# S3220A5.net
KiCad netlist of a schematic drawn in Altium Designer
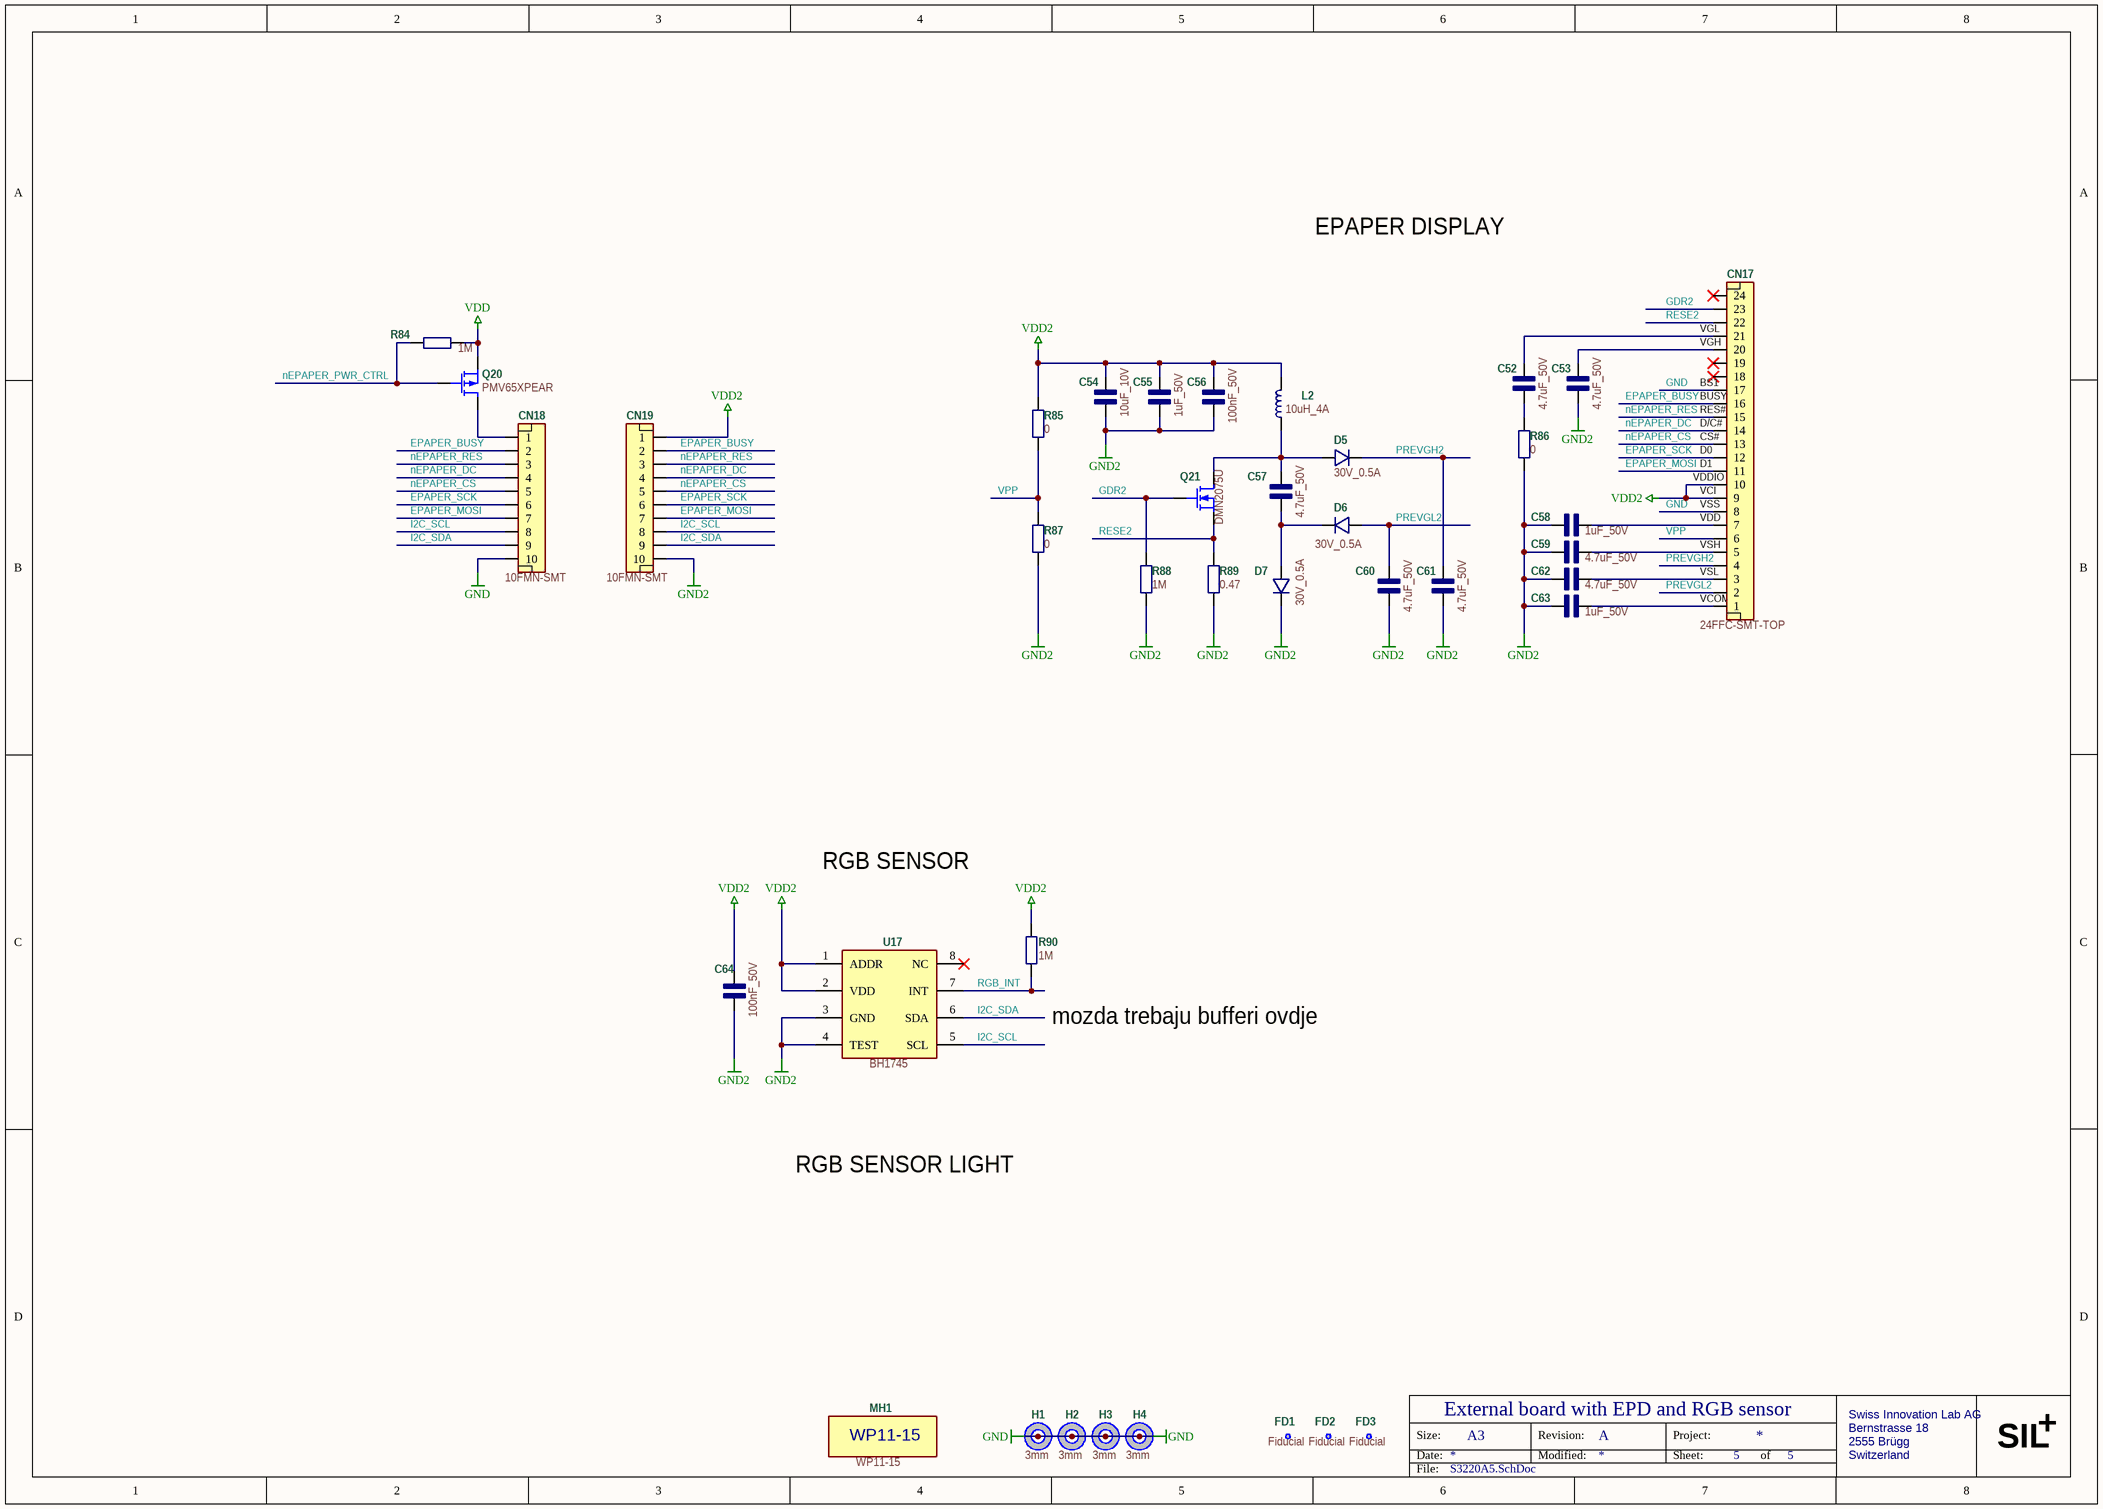
[diagram p0: S3220A5.SchDoc]

(export (version "E")
  (design (tool "Eeschema 10.0.6"))
  (components
    (comp (ref "C52")
      (value "4.7uF_50V")
      (footprint "C_1210")
      (description "4.7µF 50V Ceramic Capacitor X7R 1210 (3225 Metric) 0.126\" L x 0.098\" W (3.20mm x 2.50mm)")
      (fields
        (field (name "MANUFACTURER") "Taiyo Yuden")
        (field (name "MANUFACTURER PART NUMBER") "UMK325B7475MM-T")
      )
      (libsource (lib "") (part "C_4.7uF_50V_1"))
    )
    (comp (ref "C53")
      (value "4.7uF_50V")
      (footprint "C_1210")
      (description "4.7µF 50V Ceramic Capacitor X7R 1210 (3225 Metric) 0.126\" L x 0.098\" W (3.20mm x 2.50mm)")
      (fields
        (field (name "MANUFACTURER") "Taiyo Yuden")
        (field (name "MANUFACTURER PART NUMBER") "UMK325B7475MM-T")
      )
      (libsource (lib "") (part "C_4.7uF_50V_1"))
    )
    (comp (ref "C54")
      (value "10uF_10V")
      (footprint "SIL:C_0603")
      (description "10µF ±10% 10V Ceramic Capacitor X5R 0603 (1608 Metric)")
      (fields
        (field (name "MANUFACTURER") "Murata Electronics North America")
        (field (name "MANUFACTURER PART NUMBER") "GRM188R61A106KE69D")
      )
      (libsource (lib "SIL") (part "C_10uF_10V"))
    )
    (comp (ref "C55")
      (value "1uF_50V")
      (footprint "C_0603")
      (description "1µF 50V Ceramic Capacitor X5R 0603 (1608 Metric) 0.063\" L x 0.032\" W (1.60mm x 0.80mm)")
      (fields
        (field (name "MANUFACTURER") "Samsung Electro-Mechanics")
        (field (name "MANUFACTURER PART NUMBER") "CL10A105KB8NNNC")
      )
      (libsource (lib "") (part "C_1uF_50V_1"))
    )
    (comp (ref "C56")
      (value "100nF_50V")
      (footprint "SIL:C_0603")
      (description "0.1µF ±10% 50V Ceramic Capacitor X7R 0603 (1608 Metric)")
      (fields
        (field (name "MANUFACTURER") "TDK")
        (field (name "MANUFACTURER PART NUMBER") "C1608X7R1H104K080AA")
      )
      (libsource (lib "SIL") (part "C_100nF_50V"))
    )
    (comp (ref "C57")
      (value "4.7uF_50V")
      (footprint "C_1210")
      (description "4.7µF 50V Ceramic Capacitor X7R 1210 (3225 Metric) 0.126\" L x 0.098\" W (3.20mm x 2.50mm)")
      (fields
        (field (name "MANUFACTURER") "Taiyo Yuden")
        (field (name "MANUFACTURER PART NUMBER") "UMK325B7475MM-T")
      )
      (libsource (lib "") (part "C_4.7uF_50V_1"))
    )
    (comp (ref "C58")
      (value "1uF_50V")
      (footprint "C_0603")
      (description "1µF 50V Ceramic Capacitor X5R 0603 (1608 Metric) 0.063\" L x 0.032\" W (1.60mm x 0.80mm)")
      (fields
        (field (name "MANUFACTURER") "Samsung Electro-Mechanics")
        (field (name "MANUFACTURER PART NUMBER") "CL10A105KB8NNNC")
      )
      (libsource (lib "SIL") (part "C_1uF_50V"))
    )
    (comp (ref "C59")
      (value "4.7uF_50V")
      (footprint "C_1210")
      (description "4.7µF 50V Ceramic Capacitor X7R 1210 (3225 Metric) 0.126\" L x 0.098\" W (3.20mm x 2.50mm)")
      (fields
        (field (name "MANUFACTURER") "Taiyo Yuden")
        (field (name "MANUFACTURER PART NUMBER") "UMK325B7475MM-T")
      )
      (libsource (lib "SIL") (part "C_4.7uF_50V"))
    )
    (comp (ref "C60")
      (value "4.7uF_50V")
      (footprint "C_1210")
      (description "4.7µF 50V Ceramic Capacitor X7R 1210 (3225 Metric) 0.126\" L x 0.098\" W (3.20mm x 2.50mm)")
      (fields
        (field (name "MANUFACTURER") "Taiyo Yuden")
        (field (name "MANUFACTURER PART NUMBER") "UMK325B7475MM-T")
      )
      (libsource (lib "") (part "C_4.7uF_50V_1"))
    )
    (comp (ref "C61")
      (value "4.7uF_50V")
      (footprint "C_1210")
      (description "4.7µF 50V Ceramic Capacitor X7R 1210 (3225 Metric) 0.126\" L x 0.098\" W (3.20mm x 2.50mm)")
      (fields
        (field (name "MANUFACTURER") "Taiyo Yuden")
        (field (name "MANUFACTURER PART NUMBER") "UMK325B7475MM-T")
      )
      (libsource (lib "") (part "C_4.7uF_50V_1"))
    )
    (comp (ref "C62")
      (value "4.7uF_50V")
      (footprint "C_1210")
      (description "4.7µF 50V Ceramic Capacitor X7R 1210 (3225 Metric) 0.126\" L x 0.098\" W (3.20mm x 2.50mm)")
      (fields
        (field (name "MANUFACTURER") "Taiyo Yuden")
        (field (name "MANUFACTURER PART NUMBER") "UMK325B7475MM-T")
      )
      (libsource (lib "SIL") (part "C_4.7uF_50V"))
    )
    (comp (ref "C63")
      (value "1uF_50V")
      (footprint "C_0603")
      (description "1µF 50V Ceramic Capacitor X5R 0603 (1608 Metric) 0.063\" L x 0.032\" W (1.60mm x 0.80mm)")
      (fields
        (field (name "MANUFACTURER") "Samsung Electro-Mechanics")
        (field (name "MANUFACTURER PART NUMBER") "CL10A105KB8NNNC")
      )
      (libsource (lib "SIL") (part "C_1uF_50V"))
    )
    (comp (ref "C64")
      (value "100nF_50V")
      (footprint "SIL:C_0603")
      (description "0.1µF ±10% 50V Ceramic Capacitor X7R 0603 (1608 Metric)")
      (fields
        (field (name "MANUFACTURER") "TDK")
        (field (name "MANUFACTURER PART NUMBER") "C1608X7R1H104K080AA")
      )
      (libsource (lib "") (part "C_100nF_50V_1"))
    )
    (comp (ref "CN17")
      (value "24FFC-SMT-TOP")
      (footprint "CN_FFC-24-SMT-TOP")
      (description "24 Position FFC, FPC Connector Contacts, Top 0.020\" (0.50mm) Surface Mount, Right Angle")
      (fields
        (field (name "MANUFACTURER") "Amphenol FCI")
        (field (name "MANUFACTURER PART NUMBER") "SFV24R-2STE1HLF")
      )
      (libsource (lib "SIL") (part "CN_24FFC-SMT-TOP"))
    )
    (comp (ref "CN18")
      (value "10FMN-SMT")
      (footprint "CN_FCC-10FMN-SMT")
      (description "10 Position FFC Connector Contacts, Top 0.039\" (1.00mm) Surface Mount, Right Angle")
      (fields
        (field (name "MANUFACTURER") "JST Sales America Inc.")
        (field (name "MANUFACTURER PART NUMBER") "10FMN-SMT-A-TF(LF)(SN)")
      )
      (libsource (lib "") (part "CN_10FMN-SMT_1"))
    )
    (comp (ref "CN19")
      (value "10FMN-SMT")
      (footprint "CN_FCC-10FMN-SMT")
      (description "10 Position FFC Connector Contacts, Top 0.039\" (1.00mm) Surface Mount, Right Angle")
      (fields
        (field (name "MANUFACTURER") "JST Sales America Inc.")
        (field (name "MANUFACTURER PART NUMBER") "10FMN-SMT-A-TF(LF)(SN)")
      )
      (libsource (lib "SIL") (part "CN_10FMN-SMT"))
    )
    (comp (ref "D5")
      (value "30V_0.5A")
      (footprint "D_SOD-123")
      (description "Diode Schottky 30V 500mA Surface Mount SOD-123")
      (fields
        (field (name "MANUFACTURER") "ON Semiconductor")
        (field (name "MANUFACTURER PART NUMBER") "MBR0530")
      )
      (libsource (lib "SIL") (part "D_30V_0.5A"))
    )
    (comp (ref "D6")
      (value "30V_0.5A")
      (footprint "D_SOD-123")
      (description "Diode Schottky 30V 500mA Surface Mount SOD-123")
      (fields
        (field (name "MANUFACTURER") "ON Semiconductor")
        (field (name "MANUFACTURER PART NUMBER") "MBR0530")
      )
      (libsource (lib "SIL") (part "D_30V_0.5A"))
    )
    (comp (ref "D7")
      (value "30V_0.5A")
      (footprint "D_SOD-123")
      (description "Diode Schottky 30V 500mA Surface Mount SOD-123")
      (fields
        (field (name "MANUFACTURER") "ON Semiconductor")
        (field (name "MANUFACTURER PART NUMBER") "MBR0530")
      )
      (libsource (lib "SIL") (part "D_30V_0.5A"))
    )
    (comp (ref "FD1")
      (value "Fiducial")
      (footprint "FD_Fiducial")
      (description "Reference point for assembly machine")
      (fields (field (name "MANUFACTURER") "Swiss Innovation Lab"))
      (libsource (lib "SIL") (part "FD_Fiducial"))
    )
    (comp (ref "FD2")
      (value "Fiducial")
      (footprint "FD_Fiducial")
      (description "Reference point for assembly machine")
      (fields (field (name "MANUFACTURER") "Swiss Innovation Lab"))
      (libsource (lib "SIL") (part "FD_Fiducial"))
    )
    (comp (ref "FD3")
      (value "Fiducial")
      (footprint "FD_Fiducial")
      (description "Reference point for assembly machine")
      (fields (field (name "MANUFACTURER") "Swiss Innovation Lab"))
      (libsource (lib "SIL") (part "FD_Fiducial"))
    )
    (comp (ref "H1")
      (value "3mm")
      (footprint "H_3M_55M")
      (description "Hole 3mm, Pad 5.5mm")
      (fields (field (name "MANUFACTURER") "Swissinnolab"))
      (libsource (lib "Swissinnovationlab") (part "H_3M_55M"))
    )
    (comp (ref "H2")
      (value "3mm")
      (footprint "H_3M_55M")
      (description "Hole 3mm, Pad 5.5mm")
      (fields (field (name "MANUFACTURER") "Swissinnolab"))
      (libsource (lib "Swissinnovationlab") (part "H_3M_55M"))
    )
    (comp (ref "H3")
      (value "3mm")
      (footprint "H_3M_55M")
      (description "Hole 3mm, Pad 5.5mm")
      (fields (field (name "MANUFACTURER") "Swissinnolab"))
      (libsource (lib "Swissinnovationlab") (part "H_3M_55M"))
    )
    (comp (ref "H4")
      (value "3mm")
      (footprint "H_3M_55M")
      (description "Hole 3mm, Pad 5.5mm")
      (fields (field (name "MANUFACTURER") "Swissinnolab"))
      (libsource (lib "Swissinnovationlab") (part "H_3M_55M"))
    )
    (comp (ref "L2")
      (value "10uH_4A")
      (footprint "L_SRP6540")
      (description "10µH Shielded Wirewound Inductor 4A 78.5 mOhm Max Nonstandard")
      (fields
        (field (name "MANUFACTURER") "Bourns Inc.")
        (field (name "MANUFACTURER PART NUMBER") "SRP6540-100M")
      )
      (libsource (lib "SIL") (part "L_10uH_4A"))
    )
    (comp (ref "MH1")
      (value "WP11-15")
      (footprint "MH_WP11-15")
      (description "Case Takachi WP11-15")
      (fields (field (name "MANUFACTURER") "Takachi"))
      (libsource (lib "SIL") (part "MH_WP11-15"))
    )
    (comp (ref "Q20")
      (value "PMV65XPEAR")
      (footprint "Q_SOT23")
      (description "P-Channel 20V 2.8A (Ta) 480mW (Ta), 6.25W (Tc) Surface Mount TO-236AB (SOT23)")
      (fields (field (name "MANUFACTURER") "Nexperia USA Inc."))
      (libsource (lib "SIL") (part "Q_PMV65"))
    )
    (comp (ref "Q21")
      (value "DMN2075U")
      (footprint "Q_SOT23")
      (description "N-Channel 20V 4.2A (Ta) 800mW (Ta) Surface Mount SOT-23-3")
      (fields
        (field (name "MANUFACTURER") "Diodes Incorporated")
        (field (name "MANUFACTURER PART NUMBER") "DMN2075U-7")
      )
      (libsource (lib "SIL") (part "Q_DMN2075U"))
    )
    (comp (ref "R84")
      (value "1M")
      (footprint "SIL:R_0603")
      (description "1 MOhms ±1% 0.1W, 1/10W Chip Resistor 0603 (1608 Metric) Automotive AEC-Q200 Thick Film")
      (fields
        (field (name "MANUFACTURER") "Panasonic Electronic Components")
        (field (name "MANUFACTURER PART NUMBER") "ERJ-3EKF1004V")
      )
      (libsource (lib "SIL") (part "R_1M_1%"))
    )
    (comp (ref "R85")
      (value "0")
      (footprint "SIL:R_0603")
      (description "0 Ohms Jumper 0.1W, 1/10W Chip Resistor 0603 (1608 Metric) Automotive AEC-Q200 Thick Film")
      (fields
        (field (name "MANUFACTURER") "Panasonic Electronic Components")
        (field (name "MANUFACTURER PART NUMBER") "ERJ-3GEY0R00V")
      )
      (libsource (lib "") (part "R_0_1%_1"))
    )
    (comp (ref "R86")
      (value "0")
      (footprint "SIL:R_0603")
      (description "0 Ohms Jumper 0.1W, 1/10W Chip Resistor 0603 (1608 Metric) Automotive AEC-Q200 Thick Film")
      (fields
        (field (name "MANUFACTURER") "Panasonic Electronic Components")
        (field (name "MANUFACTURER PART NUMBER") "ERJ-3GEY0R00V")
      )
      (libsource (lib "") (part "R_0_1%_1"))
    )
    (comp (ref "R87")
      (value "0")
      (footprint "SIL:R_0603")
      (description "0 Ohms Jumper 0.1W, 1/10W Chip Resistor 0603 (1608 Metric) Automotive AEC-Q200 Thick Film")
      (fields
        (field (name "MANUFACTURER") "Panasonic Electronic Components")
        (field (name "MANUFACTURER PART NUMBER") "ERJ-3GEY0R00V")
      )
      (libsource (lib "SIL") (part "R_0_1%"))
    )
    (comp (ref "R88")
      (value "1M")
      (footprint "SIL:R_0603")
      (description "1 MOhms ±1% 0.1W, 1/10W Chip Resistor 0603 (1608 Metric) Automotive AEC-Q200 Thick Film")
      (fields
        (field (name "MANUFACTURER") "Panasonic Electronic Components")
        (field (name "MANUFACTURER PART NUMBER") "ERJ-3EKF1004V")
      )
      (libsource (lib "") (part "R_1M_1%_2"))
    )
    (comp (ref "R89")
      (value "0.47")
      (footprint "SIL:R_0603")
      (fields
        (field (name "MANUFACTURER") "Panasonic Electronic Components")
        (field (name "MANUFACTURER PART NUMBER") "ERJ-3BQFR47V")
      )
      (libsource (lib "SIL") (part "R_0.47_1%"))
    )
    (comp (ref "R90")
      (value "1M")
      (footprint "SIL:R_0603")
      (description "1 MOhms ±1% 0.1W, 1/10W Chip Resistor 0603 (1608 Metric) Automotive AEC-Q200 Thick Film")
      (fields
        (field (name "MANUFACTURER") "Panasonic Electronic Components")
        (field (name "MANUFACTURER PART NUMBER") "ERJ-3EKF1004V")
      )
      (libsource (lib "") (part "R_1M_1%_1"))
    )
    (comp (ref "U17")
      (value "BH1745")
      (footprint "U_8-WSON_2120")
      (description "Color Sensor  Standby 8-UDFN Exposed Pad")
      (fields
        (field (name "MANUFACTURER") "Rohm Semiconductor")
        (field (name "MANUFACTURER PART NUMBER") "BH1745NUC-E2")
      )
      (libsource (lib "SIL") (part "U_BH1745"))
    )
  )
  (nets
    (net (code "1") (name "/EPAPER_BUSY") (class "Default")
      (node (ref "CN17") (pin "16") (pinfunction "16_16") (pintype "passive"))
      (node (ref "CN18") (pin "2") (pinfunction "2_2") (pintype "passive"))
      (node (ref "CN19") (pin "2") (pinfunction "2_2") (pintype "passive"))
    )
    (net (code "2") (name "/EPAPER_MOSI") (class "Default")
      (node (ref "CN17") (pin "11") (pinfunction "11_11") (pintype "passive"))
      (node (ref "CN18") (pin "7") (pinfunction "7_7") (pintype "passive"))
      (node (ref "CN19") (pin "7") (pinfunction "7_7") (pintype "passive"))
    )
    (net (code "3") (name "/EPAPER_SCK") (class "Default")
      (node (ref "CN17") (pin "12") (pinfunction "12_12") (pintype "passive"))
      (node (ref "CN18") (pin "6") (pinfunction "6_6") (pintype "passive"))
      (node (ref "CN19") (pin "6") (pinfunction "6_6") (pintype "passive"))
    )
    (net (code "4") (name "/GDR2") (class "Default")
      (node (ref "CN17") (pin "23") (pinfunction "23_23") (pintype "passive"))
      (node (ref "Q21") (pin "1") (pinfunction "G_1") (pintype "passive"))
      (node (ref "R88") (pin "2") (pinfunction "2_2") (pintype "passive"))
    )
    (net (code "5") (name "/I2C_SCL") (class "Default")
      (node (ref "CN18") (pin "8") (pinfunction "8_8") (pintype "passive"))
      (node (ref "CN19") (pin "8") (pinfunction "8_8") (pintype "passive"))
      (node (ref "U17") (pin "5") (pinfunction "SCL_5") (pintype "open_collector"))
    )
    (net (code "6") (name "/I2C_SDA") (class "Default")
      (node (ref "CN18") (pin "9") (pinfunction "9_9") (pintype "passive"))
      (node (ref "CN19") (pin "9") (pinfunction "9_9") (pintype "passive"))
      (node (ref "U17") (pin "6") (pinfunction "SDA_6") (pintype "open_collector"))
    )
    (net (code "7") (name "/PREVGH2") (class "Default")
      (node (ref "C61") (pin "2") (pintype "passive"))
      (node (ref "CN17") (pin "4") (pinfunction "4_4") (pintype "passive"))
      (node (ref "D5") (pin "K") (pintype "passive"))
    )
    (net (code "8") (name "/PREVGL2") (class "Default")
      (node (ref "C60") (pin "2") (pintype "passive"))
      (node (ref "CN17") (pin "2") (pinfunction "2_2") (pintype "passive"))
      (node (ref "D6") (pin "A") (pintype "passive"))
    )
    (net (code "9") (name "/RESE2") (class "Default")
      (node (ref "CN17") (pin "22") (pinfunction "22_22") (pintype "passive"))
      (node (ref "Q21") (pin "2") (pinfunction "S_2") (pintype "passive"))
      (node (ref "R89") (pin "2") (pinfunction "2_2") (pintype "passive"))
    )
    (net (code "10") (name "/RGB_INT") (class "Default")
      (node (ref "R90") (pin "2") (pinfunction "2_2") (pintype "passive"))
      (node (ref "U17") (pin "7") (pinfunction "INT_7") (pintype "open_collector"))
    )
    (net (code "11") (name "/VPP") (class "Default")
      (node (ref "CN17") (pin "6") (pinfunction "6_6") (pintype "passive"))
      (node (ref "R85") (pin "1") (pinfunction "1_1") (pintype "passive"))
      (node (ref "R87") (pin "1") (pinfunction "1_1") (pintype "passive"))
    )
    (net (code "12") (name "/nEPAPER_CS") (class "Default")
      (node (ref "CN17") (pin "13") (pinfunction "13_13") (pintype "passive"))
      (node (ref "CN18") (pin "5") (pinfunction "5_5") (pintype "passive"))
      (node (ref "CN19") (pin "5") (pinfunction "5_5") (pintype "passive"))
    )
    (net (code "13") (name "/nEPAPER_DC") (class "Default")
      (node (ref "CN17") (pin "14") (pinfunction "14_14") (pintype "passive"))
      (node (ref "CN18") (pin "4") (pinfunction "4_4") (pintype "passive"))
      (node (ref "CN19") (pin "4") (pinfunction "4_4") (pintype "passive"))
    )
    (net (code "14") (name "/nEPAPER_PWR_CTRL") (class "Default")
      (node (ref "Q20") (pin "1") (pinfunction "G_1") (pintype "passive"))
      (node (ref "R84") (pin "1") (pinfunction "1_1") (pintype "passive"))
    )
    (net (code "15") (name "/nEPAPER_RES") (class "Default")
      (node (ref "CN17") (pin "15") (pinfunction "15_15") (pintype "passive"))
      (node (ref "CN18") (pin "3") (pinfunction "3_3") (pintype "passive"))
      (node (ref "CN19") (pin "3") (pinfunction "3_3") (pintype "passive"))
    )
    (net (code "16") (name "GND") (class "Default")
      (node (ref "CN17") (pin "17") (pinfunction "17_17") (pintype "passive"))
      (node (ref "CN17") (pin "8") (pinfunction "8_8") (pintype "passive"))
      (node (ref "CN18") (pin "10") (pinfunction "10_10") (pintype "passive"))
      (node (ref "H1") (pin "0") (pinfunction "0_0") (pintype "passive"))
      (node (ref "H2") (pin "0") (pinfunction "0_0") (pintype "passive"))
      (node (ref "H3") (pin "0") (pinfunction "0_0") (pintype "passive"))
      (node (ref "H4") (pin "0") (pinfunction "0_0") (pintype "passive"))
    )
    (net (code "17") (name "GND2") (class "Default")
      (node (ref "C53") (pin "1") (pintype "passive"))
      (node (ref "C54") (pin "1") (pintype "passive"))
      (node (ref "C55") (pin "1") (pintype "passive"))
      (node (ref "C56") (pin "1") (pintype "passive"))
      (node (ref "C58") (pin "1") (pintype "passive"))
      (node (ref "C59") (pin "2") (pintype "passive"))
      (node (ref "C60") (pin "1") (pintype "passive"))
      (node (ref "C61") (pin "1") (pintype "passive"))
      (node (ref "C62") (pin "2") (pintype "passive"))
      (node (ref "C63") (pin "1") (pintype "passive"))
      (node (ref "C64") (pin "2") (pintype "passive"))
      (node (ref "CN19") (pin "10") (pinfunction "10_10") (pintype "passive"))
      (node (ref "D7") (pin "K") (pintype "passive"))
      (node (ref "R86") (pin "1") (pinfunction "1_1") (pintype "passive"))
      (node (ref "R87") (pin "2") (pinfunction "2_2") (pintype "passive"))
      (node (ref "R88") (pin "1") (pinfunction "1_1") (pintype "passive"))
      (node (ref "R89") (pin "1") (pinfunction "1_1") (pintype "passive"))
      (node (ref "U17") (pin "3") (pinfunction "GND_3") (pintype "power_in"))
      (node (ref "U17") (pin "4") (pinfunction "TEST_4") (pintype "passive"))
    )
    (net (code "18") (name "Net-(C52-Pad1)") (class "Default")
      (node (ref "C52") (pin "1") (pintype "passive"))
      (node (ref "R86") (pin "2") (pinfunction "2_2") (pintype "passive"))
    )
    (net (code "19") (name "Net-(C52-Pad2)") (class "Default")
      (node (ref "C52") (pin "2") (pintype "passive"))
      (node (ref "CN17") (pin "21") (pinfunction "21_21") (pintype "passive"))
    )
    (net (code "20") (name "Net-(C53-Pad2)") (class "Default")
      (node (ref "C53") (pin "2") (pintype "passive"))
      (node (ref "CN17") (pin "20") (pinfunction "20_20") (pintype "passive"))
    )
    (net (code "21") (name "Net-(C57-Pad1)") (class "Default")
      (node (ref "C57") (pin "1") (pintype "passive"))
      (node (ref "D6") (pin "K") (pintype "passive"))
      (node (ref "D7") (pin "A") (pintype "passive"))
    )
    (net (code "22") (name "Net-(C58-Pad2)") (class "Default")
      (node (ref "C58") (pin "2") (pintype "passive"))
      (node (ref "CN17") (pin "7") (pinfunction "7_7") (pintype "passive"))
    )
    (net (code "23") (name "Net-(C59-Pad1)") (class "Default")
      (node (ref "C59") (pin "1") (pintype "passive"))
      (node (ref "CN17") (pin "5") (pinfunction "5_5") (pintype "passive"))
    )
    (net (code "24") (name "Net-(C62-Pad1)") (class "Default")
      (node (ref "C62") (pin "1") (pintype "passive"))
      (node (ref "CN17") (pin "3") (pinfunction "3_3") (pintype "passive"))
    )
    (net (code "25") (name "Net-(C63-Pad2)") (class "Default")
      (node (ref "C63") (pin "2") (pintype "passive"))
      (node (ref "CN17") (pin "1") (pinfunction "1_1") (pintype "passive"))
    )
    (net (code "26") (name "Net-(Q20-D)") (class "Default")
      (node (ref "CN18") (pin "1") (pinfunction "1_1") (pintype "passive"))
      (node (ref "Q20") (pin "3") (pinfunction "D_3") (pintype "passive"))
    )
    (net (code "27") (name "Net-(Q21-D)") (class "Default")
      (node (ref "C57") (pin "2") (pintype "passive"))
      (node (ref "D5") (pin "A") (pintype "passive"))
      (node (ref "L2") (pin "1") (pinfunction "1_1") (pintype "passive"))
      (node (ref "Q21") (pin "3") (pinfunction "D_3") (pintype "passive"))
    )
    (net (code "28") (name "VDD") (class "Default")
      (node (ref "Q20") (pin "2") (pinfunction "S_2") (pintype "passive"))
      (node (ref "R84") (pin "2") (pinfunction "2_2") (pintype "passive"))
    )
    (net (code "29") (name "VDD2") (class "Default")
      (node (ref "C54") (pin "2") (pintype "passive"))
      (node (ref "C55") (pin "2") (pintype "passive"))
      (node (ref "C56") (pin "2") (pintype "passive"))
      (node (ref "C64") (pin "1") (pintype "passive"))
      (node (ref "CN17") (pin "10") (pinfunction "10_10") (pintype "passive"))
      (node (ref "CN17") (pin "9") (pinfunction "9_9") (pintype "passive"))
      (node (ref "CN19") (pin "1") (pinfunction "1_1") (pintype "passive"))
      (node (ref "L2") (pin "2") (pinfunction "2_2") (pintype "passive"))
      (node (ref "R85") (pin "2") (pinfunction "2_2") (pintype "passive"))
      (node (ref "R90") (pin "1") (pinfunction "1_1") (pintype "passive"))
      (node (ref "U17") (pin "1") (pinfunction "ADDR_1") (pintype "passive"))
      (node (ref "U17") (pin "2") (pinfunction "VDD_2") (pintype "power_in"))
    )
    (net (code "30") (name "unconnected-(CN17-Pad18)") (class "Default")
      (node (ref "CN17") (pin "18") (pinfunction "18_18") (pintype "passive+no_connect"))
    )
    (net (code "31") (name "unconnected-(CN17-Pad19)") (class "Default")
      (node (ref "CN17") (pin "19") (pinfunction "19_19") (pintype "passive+no_connect"))
    )
    (net (code "32") (name "unconnected-(CN17-Pad24)") (class "Default")
      (node (ref "CN17") (pin "24") (pinfunction "24_24") (pintype "passive+no_connect"))
    )
    (net (code "33") (name "unconnected-(FD1-Pad0)") (class "Default")
      (node (ref "FD1") (pin "0") (pinfunction "0_0") (pintype "passive"))
    )
    (net (code "34") (name "unconnected-(FD2-Pad0)") (class "Default")
      (node (ref "FD2") (pin "0") (pinfunction "0_0") (pintype "passive"))
    )
    (net (code "35") (name "unconnected-(FD3-Pad0)") (class "Default")
      (node (ref "FD3") (pin "0") (pinfunction "0_0") (pintype "passive"))
    )
    (net (code "36") (name "unconnected-(MH1-Pad0)") (class "Default")
      (node (ref "MH1") (pin "0") (pinfunction "0_0") (pintype "passive"))
    )
    (net (code "37") (name "unconnected-(U17-NC-Pad8)") (class "Default")
      (node (ref "U17") (pin "8") (pinfunction "NC_8") (pintype "passive+no_connect"))
    )
  )
)
